# 12V_LDO_3_3V.net
KiCad netlist of a schematic drawn in Altium Designer
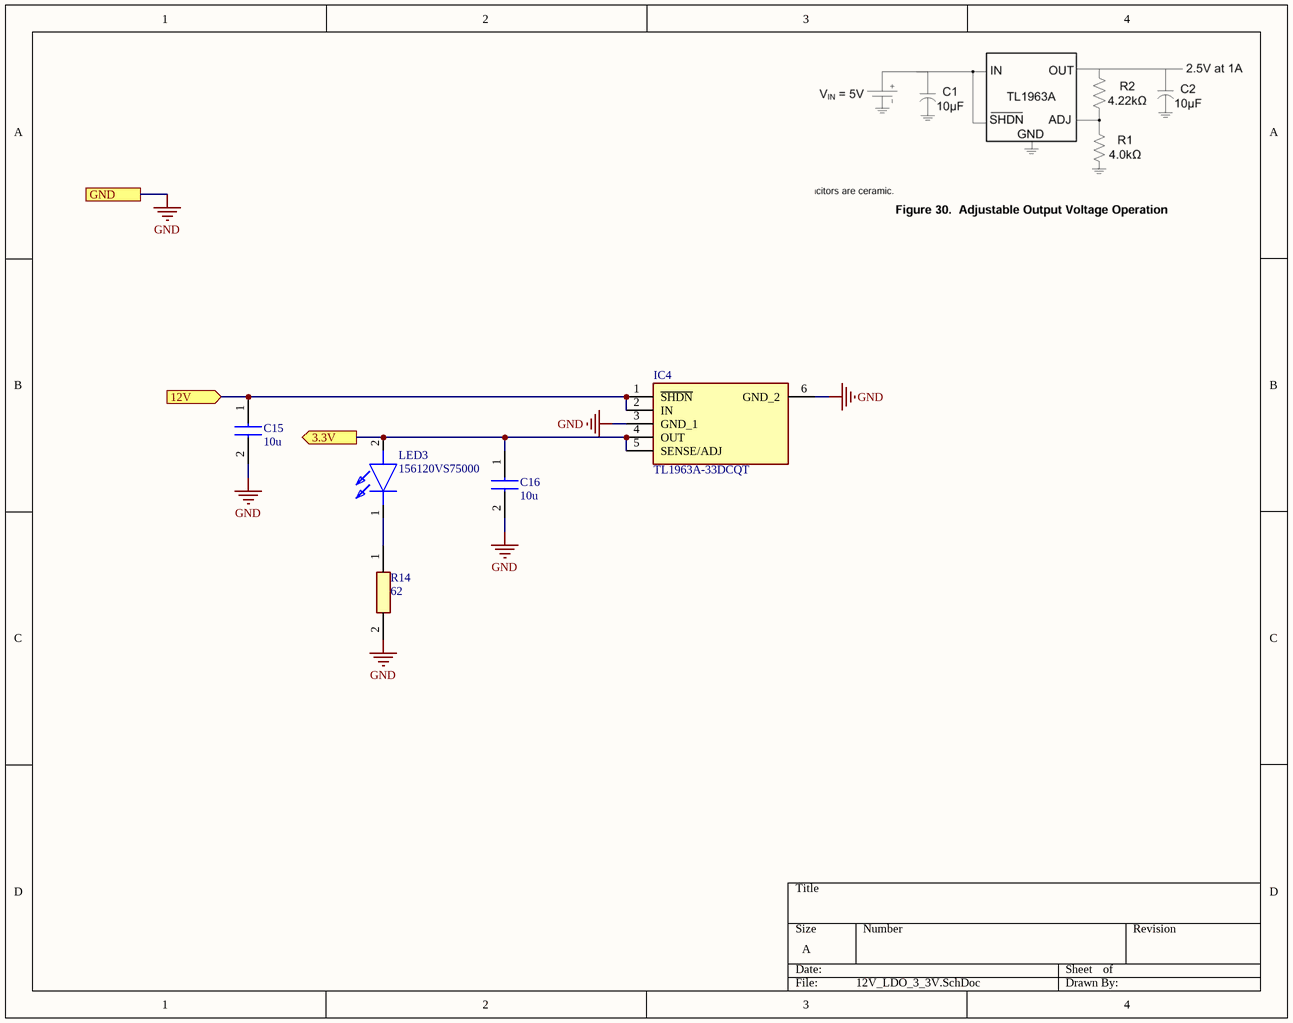
[diagram p0: 12V_LDO_3_3V.SchDoc]

(export (version "E")
  (design (tool "Eeschema 10.0.6"))
  (components
    (comp (ref "C15")
      (value "10u")
      (footprint "SamacSys:CAPC3216X180N")
      (description "Capacitor")
      (fields (field (name "MANUFACTURER_PART_NUMBER") "MLASU31LBB5106KTNA01"))
      (libsource (lib "SamacSys") (part "MLASU31LBB5106KTNA01"))
    )
    (comp (ref "C16")
      (value "10u")
      (footprint "SamacSys:CAPC3216X180N")
      (description "Capacitor")
      (fields (field (name "MANUFACTURER_PART_NUMBER") "MLASU31LBB5106KTNA01"))
      (libsource (lib "SamacSys") (part "MLASU31LBB5106KTNA01"))
    )
    (comp (ref "IC4")
      (value "TL1963A-33DCQT")
      (footprint "SamacSys:SOT127P706X180-6N")
      (description "Integrated Circuit")
      (fields (field (name "MOUSER PART NUMBER") "595-TL1963A-33DCQT"))
      (libsource (lib "SamacSys") (part "TL1963A-33DCQT"))
    )
    (comp (ref "LED3")
      (value "156120VS75000")
      (footprint "SamacSys:156120VS75000")
      (description "LED")
      (fields (field (name "MOUSER PART NUMBER") "710-156120VS75000"))
      (libsource (lib "SamacSys") (part "156120VS75000"))
    )
    (comp (ref "R14")
      (value "62")
      (footprint "SamacSys:RESC3216X60N")
      (description "Resistor")
      (fields
        (field (name "MANUFACTURER_PART_NUMBER") "CRCW120662R0FKTA")
        (field (name "MOUSER PART NUMBER") "71-CRCW1206-62")
      )
      (libsource (lib "SamacSys") (part "CRCW120662R0FKTA"))
    )
  )
  (nets
    (net (code "1") (name "/3.3V") (class "Default")
      (node (ref "C16") (pin "1") (pinfunction "1_1") (pintype "passive"))
      (node (ref "IC4") (pin "4") (pinfunction "OUT_4") (pintype "passive"))
      (node (ref "IC4") (pin "5") (pinfunction "SENSE/ADJ_5") (pintype "passive"))
      (node (ref "LED3") (pin "2") (pinfunction "A_2") (pintype "passive"))
    )
    (net (code "2") (name "/12V") (class "Default")
      (node (ref "C15") (pin "1") (pinfunction "1_1") (pintype "passive"))
      (node (ref "IC4") (pin "1") (pinfunction "~{SHDN}_1") (pintype "passive"))
      (node (ref "IC4") (pin "2") (pinfunction "IN_2") (pintype "passive"))
    )
    (net (code "3") (name "GND") (class "Default")
      (node (ref "C15") (pin "2") (pinfunction "2_2") (pintype "passive"))
      (node (ref "C16") (pin "2") (pinfunction "2_2") (pintype "passive"))
      (node (ref "IC4") (pin "3") (pinfunction "GND_1_3") (pintype "passive"))
      (node (ref "IC4") (pin "6") (pinfunction "GND_2_6") (pintype "passive"))
      (node (ref "R14") (pin "2") (pinfunction "2_2") (pintype "passive"))
    )
    (net (code "4") (name "Net-(LED3-K)") (class "Default")
      (node (ref "LED3") (pin "1") (pinfunction "K_1") (pintype "passive"))
      (node (ref "R14") (pin "1") (pinfunction "1_1") (pintype "passive"))
    )
  )
)
